# XMC4500.net
KiCad netlist of a schematic drawn in Altium Designer
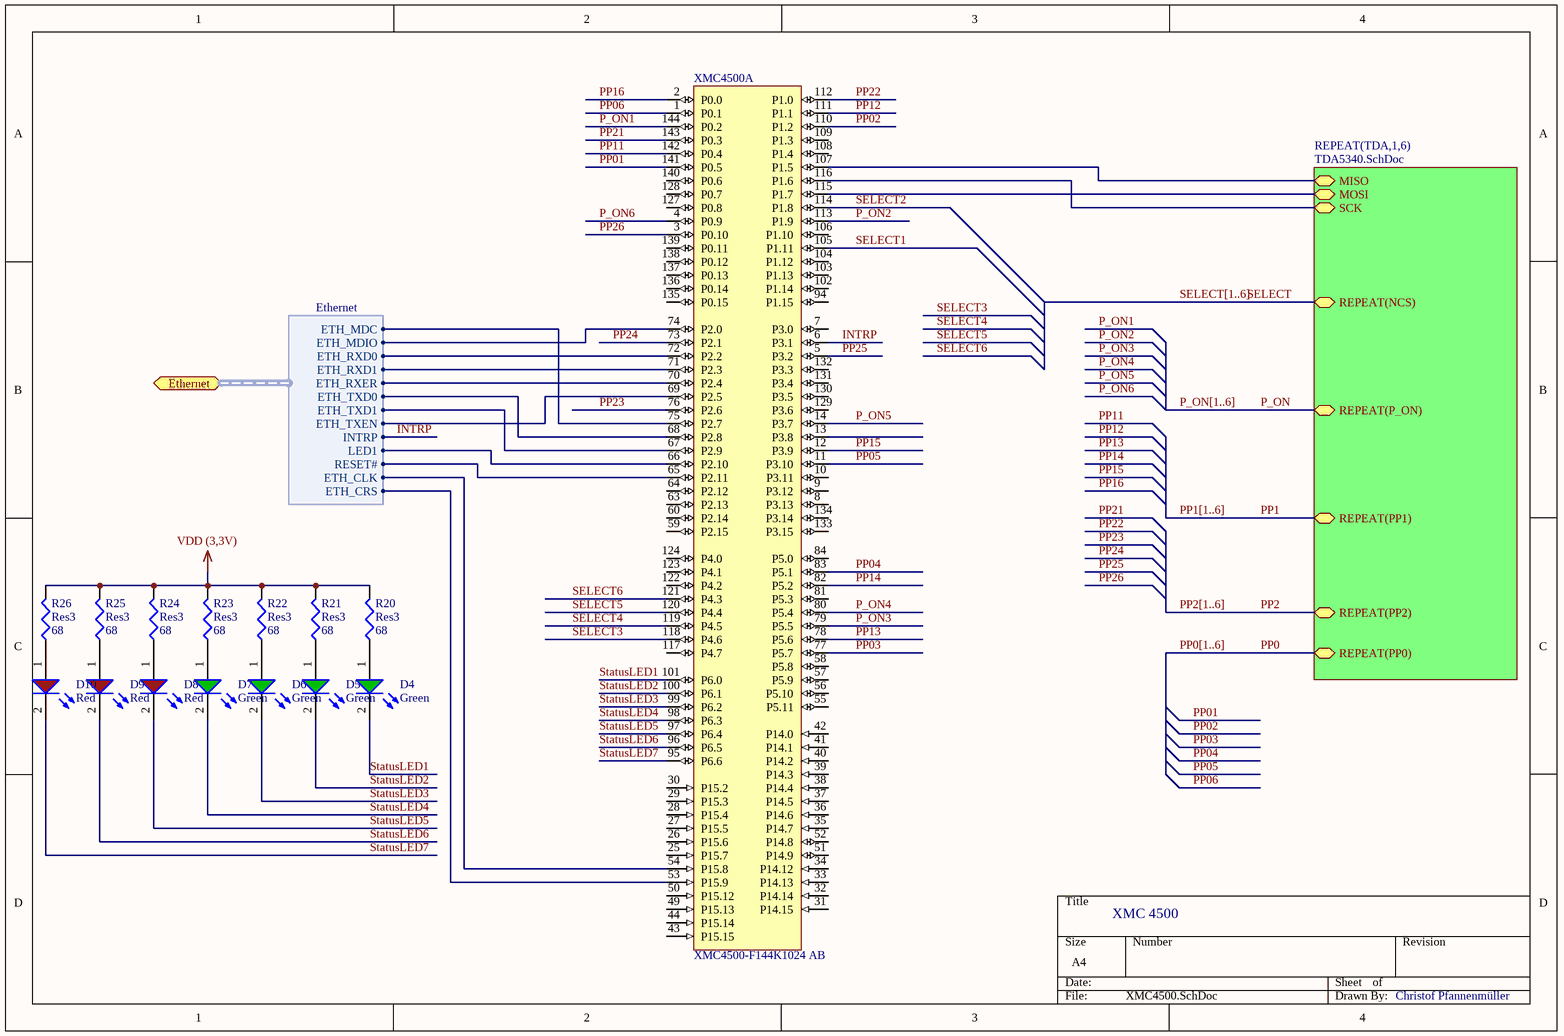
[diagram p0: XMC4500.SchDoc]

(export (version "E")
  (design (tool "Eeschema 10.0.6"))
  (components
    (comp (ref "D4")
      (value "Green")
      (footprint "LED_0805_Green")
      (description "SMD mono-color Chip LED, WL-SMCW, Green")
      (fields
        (field (name "PARTNO") "150080GS75000")
        (field (name "MANUFACTURER") "W黵th Elektronik eiSos GmbH")
        (field (name "CREATED BY") "Christin Otto")
      )
      (libsource (lib "WL-SMCW_rev15b") (part "WL-SMCW 0805  150080GS75000"))
    )
    (comp (ref "D5")
      (value "Green")
      (footprint "LED_0805_Green")
      (description "SMD mono-color Chip LED, WL-SMCW, Green")
      (fields
        (field (name "PARTNO") "150080GS75000")
        (field (name "MANUFACTURER") "W黵th Elektronik eiSos GmbH")
        (field (name "CREATED BY") "Christin Otto")
      )
      (libsource (lib "WL-SMCW_rev15b") (part "WL-SMCW 0805  150080GS75000"))
    )
    (comp (ref "D6")
      (value "Green")
      (footprint "LED_0805_Green")
      (description "SMD mono-color Chip LED, WL-SMCW, Green")
      (fields
        (field (name "PARTNO") "150080GS75000")
        (field (name "MANUFACTURER") "W黵th Elektronik eiSos GmbH")
        (field (name "CREATED BY") "Christin Otto")
      )
      (libsource (lib "WL-SMCW_rev15b") (part "WL-SMCW 0805  150080GS75000"))
    )
    (comp (ref "D7")
      (value "Green")
      (footprint "LED_0805_Green")
      (description "SMD mono-color Chip LED, WL-SMCW, Green")
      (fields
        (field (name "PARTNO") "150080GS75000")
        (field (name "MANUFACTURER") "W黵th Elektronik eiSos GmbH")
        (field (name "CREATED BY") "Christin Otto")
      )
      (libsource (lib "WL-SMCW_rev15b") (part "WL-SMCW 0805  150080GS75000"))
    )
    (comp (ref "D8")
      (value "Red")
      (footprint "LED_0805_Red")
      (description "SMD mono-color Chip LED, WL-SMCW, Red")
      (fields
        (field (name "PARTNO") "150080RS75000")
        (field (name "MANUFACTURER") "W黵th Elektronik eiSos GmbH")
        (field (name "CREATED BY") "Christin Otto")
      )
      (libsource (lib "WL-SMCW_rev15b") (part "WL-SMCW 0805  150080RS75000"))
    )
    (comp (ref "D9")
      (value "Red")
      (footprint "LED_0805_Red")
      (description "SMD mono-color Chip LED, WL-SMCW, Red")
      (fields
        (field (name "PARTNO") "150080RS75000")
        (field (name "MANUFACTURER") "W黵th Elektronik eiSos GmbH")
        (field (name "CREATED BY") "Christin Otto")
      )
      (libsource (lib "WL-SMCW_rev15b") (part "WL-SMCW 0805  150080RS75000"))
    )
    (comp (ref "D10")
      (value "Red")
      (footprint "LED_0805_Red")
      (description "SMD mono-color Chip LED, WL-SMCW, Red")
      (fields
        (field (name "PARTNO") "150080RS75000")
        (field (name "MANUFACTURER") "W黵th Elektronik eiSos GmbH")
        (field (name "CREATED BY") "Christin Otto")
      )
      (libsource (lib "WL-SMCW_rev15b") (part "WL-SMCW 0805  150080RS75000"))
    )
    (comp (ref "R20")
      (value "Res3")
      (footprint "J1-0603")
      (description "Resistor")
      (fields (field (name "ALTIUM_VALUE") "68") (field (name "PUBLISHER") "Altium Limited"))
      (libsource (lib "Miscellaneous Devices") (part "Res3"))
    )
    (comp (ref "R21")
      (value "Res3")
      (footprint "J1-0603")
      (description "Resistor")
      (fields (field (name "ALTIUM_VALUE") "68") (field (name "PUBLISHER") "Altium Limited"))
      (libsource (lib "Miscellaneous Devices") (part "Res3"))
    )
    (comp (ref "R22")
      (value "Res3")
      (footprint "J1-0603")
      (description "Resistor")
      (fields (field (name "ALTIUM_VALUE") "68") (field (name "PUBLISHER") "Altium Limited"))
      (libsource (lib "Miscellaneous Devices") (part "Res3"))
    )
    (comp (ref "R23")
      (value "Res3")
      (footprint "J1-0603")
      (description "Resistor")
      (fields (field (name "ALTIUM_VALUE") "68") (field (name "PUBLISHER") "Altium Limited"))
      (libsource (lib "Miscellaneous Devices") (part "Res3"))
    )
    (comp (ref "R24")
      (value "Res3")
      (footprint "J1-0603")
      (description "Resistor")
      (fields (field (name "ALTIUM_VALUE") "68") (field (name "PUBLISHER") "Altium Limited"))
      (libsource (lib "Miscellaneous Devices") (part "Res3"))
    )
    (comp (ref "R25")
      (value "Res3")
      (footprint "J1-0603")
      (description "Resistor")
      (fields (field (name "ALTIUM_VALUE") "68") (field (name "PUBLISHER") "Altium Limited"))
      (libsource (lib "Miscellaneous Devices") (part "Res3"))
    )
    (comp (ref "R26")
      (value "Res3")
      (footprint "J1-0603")
      (description "Resistor")
      (fields (field (name "ALTIUM_VALUE") "68") (field (name "PUBLISHER") "Altium Limited"))
      (libsource (lib "Miscellaneous Devices") (part "Res3"))
    )
    (comp (ref "XMC4500")
      (value "XMC4500-F144K1024 AB")
      (footprint "INF-PG-LQFP-144-18-6500X6500TP_N")
      (fields (field (name "MANUFACTURER") "Infineon"))
      (libsource (lib "Infineon XMC4000") (part "XMC4500-F144K1024 AB"))
    )
  )
  (nets
    (net (code "2") (name "/ETH_CLK") (class "Default")
      (node (ref "XMC4500") (pin "54") (pinfunction "P15.8_54") (pintype "input"))
    )
    (net (code "3") (name "/ETH_CRS") (class "Default")
      (node (ref "XMC4500") (pin "53") (pinfunction "P15.9_53") (pintype "input"))
    )
    (net (code "4") (name "/ETH_MDC") (class "Default")
      (node (ref "XMC4500") (pin "75") (pinfunction "P2.7_75") (pintype "bidirectional"))
    )
    (net (code "5") (name "/ETH_MDIO") (class "Default")
      (node (ref "XMC4500") (pin "74") (pinfunction "P2.0_74") (pintype "bidirectional"))
    )
    (net (code "6") (name "/ETH_RXD0") (class "Default")
      (node (ref "XMC4500") (pin "72") (pinfunction "P2.2_72") (pintype "bidirectional"))
    )
    (net (code "7") (name "/ETH_RXD1") (class "Default")
      (node (ref "XMC4500") (pin "71") (pinfunction "P2.3_71") (pintype "bidirectional"))
    )
    (net (code "8") (name "/ETH_RXER") (class "Default")
      (node (ref "XMC4500") (pin "70") (pinfunction "P2.4_70") (pintype "bidirectional"))
    )
    (net (code "9") (name "/ETH_TXD0") (class "Default")
      (node (ref "XMC4500") (pin "68") (pinfunction "P2.8_68") (pintype "bidirectional"))
    )
    (net (code "10") (name "/ETH_TXD1") (class "Default")
      (node (ref "XMC4500") (pin "67") (pinfunction "P2.9_67") (pintype "bidirectional"))
    )
    (net (code "11") (name "/ETH_TXEN") (class "Default")
      (node (ref "XMC4500") (pin "69") (pinfunction "P2.5_69") (pintype "bidirectional"))
    )
    (net (code "12") (name "/INTRP") (class "Default")
      (node (ref "XMC4500") (pin "6") (pinfunction "P3.1_6") (pintype "bidirectional"))
    )
    (net (code "13") (name "/LED1") (class "Default")
      (node (ref "XMC4500") (pin "66") (pinfunction "P2.10_66") (pintype "bidirectional"))
    )
    (net (code "14") (name "/MISO") (class "Default")
      (node (ref "XMC4500") (pin "107") (pinfunction "P1.5_107") (pintype "bidirectional"))
    )
    (net (code "15") (name "/MOSI") (class "Default")
      (node (ref "XMC4500") (pin "115") (pinfunction "P1.7_115") (pintype "bidirectional"))
    )
    (net (code "18") (name "/PP01") (class "Default")
      (node (ref "XMC4500") (pin "141") (pinfunction "P0.5_141") (pintype "bidirectional"))
    )
    (net (code "22") (name "/PP02") (class "Default")
      (node (ref "XMC4500") (pin "110") (pinfunction "P1.2_110") (pintype "bidirectional"))
    )
    (net (code "24") (name "/PP03") (class "Default")
      (node (ref "XMC4500") (pin "77") (pinfunction "P5.7_77") (pintype "bidirectional"))
    )
    (net (code "25") (name "/PP04") (class "Default")
      (node (ref "XMC4500") (pin "83") (pinfunction "P5.1_83") (pintype "bidirectional"))
    )
    (net (code "26") (name "/PP05") (class "Default")
      (node (ref "XMC4500") (pin "11") (pinfunction "P3.10_11") (pintype "bidirectional"))
    )
    (net (code "27") (name "/PP06") (class "Default")
      (node (ref "XMC4500") (pin "1") (pinfunction "P0.1_1") (pintype "bidirectional"))
    )
    (net (code "28") (name "/PP11") (class "Default")
      (node (ref "XMC4500") (pin "142") (pinfunction "P0.4_142") (pintype "bidirectional"))
    )
    (net (code "29") (name "/PP12") (class "Default")
      (node (ref "XMC4500") (pin "111") (pinfunction "P1.1_111") (pintype "bidirectional"))
    )
    (net (code "30") (name "/PP13") (class "Default")
      (node (ref "XMC4500") (pin "78") (pinfunction "P5.6_78") (pintype "bidirectional"))
    )
    (net (code "31") (name "/PP14") (class "Default")
      (node (ref "XMC4500") (pin "82") (pinfunction "P5.2_82") (pintype "bidirectional"))
    )
    (net (code "32") (name "/PP15") (class "Default")
      (node (ref "XMC4500") (pin "12") (pinfunction "P3.9_12") (pintype "bidirectional"))
    )
    (net (code "33") (name "/PP16") (class "Default")
      (node (ref "XMC4500") (pin "2") (pinfunction "P0.0_2") (pintype "bidirectional"))
    )
    (net (code "34") (name "/PP21") (class "Default")
      (node (ref "XMC4500") (pin "143") (pinfunction "P0.3_143") (pintype "bidirectional"))
    )
    (net (code "35") (name "/PP22") (class "Default")
      (node (ref "XMC4500") (pin "112") (pinfunction "P1.0_112") (pintype "bidirectional"))
    )
    (net (code "36") (name "/PP23") (class "Default")
      (node (ref "XMC4500") (pin "76") (pinfunction "P2.6_76") (pintype "bidirectional"))
    )
    (net (code "37") (name "/PP24") (class "Default")
      (node (ref "XMC4500") (pin "73") (pinfunction "P2.1_73") (pintype "bidirectional"))
    )
    (net (code "38") (name "/PP25") (class "Default")
      (node (ref "XMC4500") (pin "5") (pinfunction "P3.2_5") (pintype "bidirectional"))
    )
    (net (code "39") (name "/PP26") (class "Default")
      (node (ref "XMC4500") (pin "3") (pinfunction "P0.10_3") (pintype "bidirectional"))
    )
    (net (code "41") (name "/P_ON1") (class "Default")
      (node (ref "XMC4500") (pin "144") (pinfunction "P0.2_144") (pintype "bidirectional"))
    )
    (net (code "42") (name "/P_ON2") (class "Default")
      (node (ref "XMC4500") (pin "113") (pinfunction "P1.9_113") (pintype "bidirectional"))
    )
    (net (code "43") (name "/P_ON3") (class "Default")
      (node (ref "XMC4500") (pin "79") (pinfunction "P5.5_79") (pintype "bidirectional"))
    )
    (net (code "44") (name "/P_ON4") (class "Default")
      (node (ref "XMC4500") (pin "80") (pinfunction "P5.4_80") (pintype "bidirectional"))
    )
    (net (code "45") (name "/P_ON5") (class "Default")
      (node (ref "XMC4500") (pin "14") (pinfunction "P3.7_14") (pintype "bidirectional"))
    )
    (net (code "46") (name "/P_ON6") (class "Default")
      (node (ref "XMC4500") (pin "4") (pinfunction "P0.9_4") (pintype "bidirectional"))
    )
    (net (code "48") (name "/RESET#") (class "Default")
      (node (ref "XMC4500") (pin "65") (pinfunction "P2.11_65") (pintype "bidirectional"))
    )
    (net (code "49") (name "/SCK") (class "Default")
      (node (ref "XMC4500") (pin "116") (pinfunction "P1.6_116") (pintype "bidirectional"))
    )
    (net (code "51") (name "/SELECT1") (class "Default")
      (node (ref "XMC4500") (pin "105") (pinfunction "P1.11_105") (pintype "bidirectional"))
    )
    (net (code "52") (name "/SELECT2") (class "Default")
      (node (ref "XMC4500") (pin "114") (pinfunction "P1.8_114") (pintype "bidirectional"))
    )
    (net (code "53") (name "/SELECT3") (class "Default")
      (node (ref "XMC4500") (pin "118") (pinfunction "P4.6_118") (pintype "bidirectional"))
    )
    (net (code "54") (name "/SELECT4") (class "Default")
      (node (ref "XMC4500") (pin "119") (pinfunction "P4.5_119") (pintype "bidirectional"))
    )
    (net (code "55") (name "/SELECT5") (class "Default")
      (node (ref "XMC4500") (pin "120") (pinfunction "P4.4_120") (pintype "bidirectional"))
    )
    (net (code "56") (name "/SELECT6") (class "Default")
      (node (ref "XMC4500") (pin "121") (pinfunction "P4.3_121") (pintype "bidirectional"))
    )
    (net (code "58") (name "/StatusLED1") (class "Default")
      (node (ref "D4") (pin "2") (pinfunction "C_2") (pintype "passive"))
      (node (ref "XMC4500") (pin "101") (pinfunction "P6.0_101") (pintype "bidirectional"))
    )
    (net (code "59") (name "/StatusLED2") (class "Default")
      (node (ref "D5") (pin "2") (pinfunction "C_2") (pintype "passive"))
      (node (ref "XMC4500") (pin "100") (pinfunction "P6.1_100") (pintype "bidirectional"))
    )
    (net (code "60") (name "/StatusLED3") (class "Default")
      (node (ref "D6") (pin "2") (pinfunction "C_2") (pintype "passive"))
      (node (ref "XMC4500") (pin "99") (pinfunction "P6.2_99") (pintype "bidirectional"))
    )
    (net (code "61") (name "/StatusLED4") (class "Default")
      (node (ref "D7") (pin "2") (pinfunction "C_2") (pintype "passive"))
      (node (ref "XMC4500") (pin "98") (pinfunction "P6.3_98") (pintype "bidirectional"))
    )
    (net (code "62") (name "/StatusLED5") (class "Default")
      (node (ref "D8") (pin "2") (pinfunction "C_2") (pintype "passive"))
      (node (ref "XMC4500") (pin "97") (pinfunction "P6.4_97") (pintype "bidirectional"))
    )
    (net (code "63") (name "/StatusLED6") (class "Default")
      (node (ref "D9") (pin "2") (pinfunction "C_2") (pintype "passive"))
      (node (ref "XMC4500") (pin "96") (pinfunction "P6.5_96") (pintype "bidirectional"))
    )
    (net (code "64") (name "/StatusLED7") (class "Default")
      (node (ref "D10") (pin "2") (pinfunction "C_2") (pintype "passive"))
      (node (ref "XMC4500") (pin "95") (pinfunction "P6.6_95") (pintype "bidirectional"))
    )
    (net (code "66") (name "Net-(D4-A)") (class "Default")
      (node (ref "D4") (pin "1") (pinfunction "A_1") (pintype "passive"))
      (node (ref "R20") (pin "1") (pinfunction "1_1") (pintype "passive"))
    )
    (net (code "67") (name "Net-(D5-A)") (class "Default")
      (node (ref "D5") (pin "1") (pinfunction "A_1") (pintype "passive"))
      (node (ref "R21") (pin "1") (pinfunction "1_1") (pintype "passive"))
    )
    (net (code "68") (name "Net-(D6-A)") (class "Default")
      (node (ref "D6") (pin "1") (pinfunction "A_1") (pintype "passive"))
      (node (ref "R22") (pin "1") (pinfunction "1_1") (pintype "passive"))
    )
    (net (code "69") (name "Net-(D7-A)") (class "Default")
      (node (ref "D7") (pin "1") (pinfunction "A_1") (pintype "passive"))
      (node (ref "R23") (pin "1") (pinfunction "1_1") (pintype "passive"))
    )
    (net (code "70") (name "Net-(D8-A)") (class "Default")
      (node (ref "D8") (pin "1") (pinfunction "A_1") (pintype "passive"))
      (node (ref "R24") (pin "1") (pinfunction "1_1") (pintype "passive"))
    )
    (net (code "71") (name "Net-(D9-A)") (class "Default")
      (node (ref "D9") (pin "1") (pinfunction "A_1") (pintype "passive"))
      (node (ref "R25") (pin "1") (pinfunction "1_1") (pintype "passive"))
    )
    (net (code "72") (name "Net-(D10-A)") (class "Default")
      (node (ref "D10") (pin "1") (pinfunction "A_1") (pintype "passive"))
      (node (ref "R26") (pin "1") (pinfunction "1_1") (pintype "passive"))
    )
    (net (code "73") (name "VDD (3,3V)") (class "Default")
      (node (ref "R20") (pin "2") (pinfunction "2_2") (pintype "passive"))
      (node (ref "R21") (pin "2") (pinfunction "2_2") (pintype "passive"))
      (node (ref "R22") (pin "2") (pinfunction "2_2") (pintype "passive"))
      (node (ref "R23") (pin "2") (pinfunction "2_2") (pintype "passive"))
      (node (ref "R24") (pin "2") (pinfunction "2_2") (pintype "passive"))
      (node (ref "R25") (pin "2") (pinfunction "2_2") (pintype "passive"))
      (node (ref "R26") (pin "2") (pinfunction "2_2") (pintype "passive"))
    )
    (net (code "74") (name "unconnected-(XMC4500A-P0.6-Pad140)") (class "Default")
      (node (ref "XMC4500") (pin "140") (pinfunction "P0.6_140") (pintype "bidirectional"))
    )
    (net (code "75") (name "unconnected-(XMC4500A-P0.7-Pad128)") (class "Default")
      (node (ref "XMC4500") (pin "128") (pinfunction "P0.7_128") (pintype "bidirectional"))
    )
    (net (code "76") (name "unconnected-(XMC4500A-P0.8-Pad127)") (class "Default")
      (node (ref "XMC4500") (pin "127") (pinfunction "P0.8_127") (pintype "bidirectional"))
    )
    (net (code "77") (name "unconnected-(XMC4500A-P0.11-Pad139)") (class "Default")
      (node (ref "XMC4500") (pin "139") (pinfunction "P0.11_139") (pintype "bidirectional"))
    )
    (net (code "78") (name "unconnected-(XMC4500A-P0.12-Pad138)") (class "Default")
      (node (ref "XMC4500") (pin "138") (pinfunction "P0.12_138") (pintype "bidirectional"))
    )
    (net (code "79") (name "unconnected-(XMC4500A-P0.13-Pad137)") (class "Default")
      (node (ref "XMC4500") (pin "137") (pinfunction "P0.13_137") (pintype "bidirectional"))
    )
    (net (code "80") (name "unconnected-(XMC4500A-P0.14-Pad136)") (class "Default")
      (node (ref "XMC4500") (pin "136") (pinfunction "P0.14_136") (pintype "bidirectional"))
    )
    (net (code "81") (name "unconnected-(XMC4500A-P0.15-Pad135)") (class "Default")
      (node (ref "XMC4500") (pin "135") (pinfunction "P0.15_135") (pintype "bidirectional"))
    )
    (net (code "82") (name "unconnected-(XMC4500A-P1.3-Pad109)") (class "Default")
      (node (ref "XMC4500") (pin "109") (pinfunction "P1.3_109") (pintype "bidirectional"))
    )
    (net (code "83") (name "unconnected-(XMC4500A-P1.4-Pad108)") (class "Default")
      (node (ref "XMC4500") (pin "108") (pinfunction "P1.4_108") (pintype "bidirectional"))
    )
    (net (code "84") (name "unconnected-(XMC4500A-P1.10-Pad106)") (class "Default")
      (node (ref "XMC4500") (pin "106") (pinfunction "P1.10_106") (pintype "bidirectional"))
    )
    (net (code "85") (name "unconnected-(XMC4500A-P1.12-Pad104)") (class "Default")
      (node (ref "XMC4500") (pin "104") (pinfunction "P1.12_104") (pintype "bidirectional"))
    )
    (net (code "86") (name "unconnected-(XMC4500A-P1.13-Pad103)") (class "Default")
      (node (ref "XMC4500") (pin "103") (pinfunction "P1.13_103") (pintype "bidirectional"))
    )
    (net (code "87") (name "unconnected-(XMC4500A-P1.14-Pad102)") (class "Default")
      (node (ref "XMC4500") (pin "102") (pinfunction "P1.14_102") (pintype "bidirectional"))
    )
    (net (code "88") (name "unconnected-(XMC4500A-P1.15-Pad94)") (class "Default")
      (node (ref "XMC4500") (pin "94") (pinfunction "P1.15_94") (pintype "bidirectional"))
    )
    (net (code "89") (name "unconnected-(XMC4500A-P2.12-Pad64)") (class "Default")
      (node (ref "XMC4500") (pin "64") (pinfunction "P2.12_64") (pintype "bidirectional"))
    )
    (net (code "90") (name "unconnected-(XMC4500A-P2.13-Pad63)") (class "Default")
      (node (ref "XMC4500") (pin "63") (pinfunction "P2.13_63") (pintype "bidirectional"))
    )
    (net (code "91") (name "unconnected-(XMC4500A-P2.14-Pad60)") (class "Default")
      (node (ref "XMC4500") (pin "60") (pinfunction "P2.14_60") (pintype "bidirectional"))
    )
    (net (code "92") (name "unconnected-(XMC4500A-P2.15-Pad59)") (class "Default")
      (node (ref "XMC4500") (pin "59") (pinfunction "P2.15_59") (pintype "bidirectional"))
    )
    (net (code "93") (name "unconnected-(XMC4500A-P3.0-Pad7)") (class "Default")
      (node (ref "XMC4500") (pin "7") (pinfunction "P3.0_7") (pintype "bidirectional"))
    )
    (net (code "94") (name "unconnected-(XMC4500A-P3.3-Pad132)") (class "Default")
      (node (ref "XMC4500") (pin "132") (pinfunction "P3.3_132") (pintype "bidirectional"))
    )
    (net (code "95") (name "unconnected-(XMC4500A-P3.4-Pad131)") (class "Default")
      (node (ref "XMC4500") (pin "131") (pinfunction "P3.4_131") (pintype "bidirectional"))
    )
    (net (code "96") (name "unconnected-(XMC4500A-P3.5-Pad130)") (class "Default")
      (node (ref "XMC4500") (pin "130") (pinfunction "P3.5_130") (pintype "bidirectional"))
    )
    (net (code "97") (name "unconnected-(XMC4500A-P3.6-Pad129)") (class "Default")
      (node (ref "XMC4500") (pin "129") (pinfunction "P3.6_129") (pintype "bidirectional"))
    )
    (net (code "98") (name "unconnected-(XMC4500A-P3.8-Pad13)") (class "Default")
      (node (ref "XMC4500") (pin "13") (pinfunction "P3.8_13") (pintype "bidirectional"))
    )
    (net (code "99") (name "unconnected-(XMC4500A-P3.11-Pad10)") (class "Default")
      (node (ref "XMC4500") (pin "10") (pinfunction "P3.11_10") (pintype "bidirectional"))
    )
    (net (code "100") (name "unconnected-(XMC4500A-P3.12-Pad9)") (class "Default")
      (node (ref "XMC4500") (pin "9") (pinfunction "P3.12_9") (pintype "bidirectional"))
    )
    (net (code "101") (name "unconnected-(XMC4500A-P3.13-Pad8)") (class "Default")
      (node (ref "XMC4500") (pin "8") (pinfunction "P3.13_8") (pintype "bidirectional"))
    )
    (net (code "102") (name "unconnected-(XMC4500A-P3.14-Pad134)") (class "Default")
      (node (ref "XMC4500") (pin "134") (pinfunction "P3.14_134") (pintype "bidirectional"))
    )
    (net (code "103") (name "unconnected-(XMC4500A-P3.15-Pad133)") (class "Default")
      (node (ref "XMC4500") (pin "133") (pinfunction "P3.15_133") (pintype "bidirectional"))
    )
    (net (code "104") (name "unconnected-(XMC4500A-P4.0-Pad124)") (class "Default")
      (node (ref "XMC4500") (pin "124") (pinfunction "P4.0_124") (pintype "bidirectional"))
    )
    (net (code "105") (name "unconnected-(XMC4500A-P4.1-Pad123)") (class "Default")
      (node (ref "XMC4500") (pin "123") (pinfunction "P4.1_123") (pintype "bidirectional"))
    )
    (net (code "106") (name "unconnected-(XMC4500A-P4.2-Pad122)") (class "Default")
      (node (ref "XMC4500") (pin "122") (pinfunction "P4.2_122") (pintype "bidirectional"))
    )
    (net (code "107") (name "unconnected-(XMC4500A-P4.7-Pad117)") (class "Default")
      (node (ref "XMC4500") (pin "117") (pinfunction "P4.7_117") (pintype "bidirectional"))
    )
    (net (code "108") (name "unconnected-(XMC4500A-P5.0-Pad84)") (class "Default")
      (node (ref "XMC4500") (pin "84") (pinfunction "P5.0_84") (pintype "bidirectional"))
    )
    (net (code "109") (name "unconnected-(XMC4500A-P5.3-Pad81)") (class "Default")
      (node (ref "XMC4500") (pin "81") (pinfunction "P5.3_81") (pintype "bidirectional"))
    )
    (net (code "110") (name "unconnected-(XMC4500A-P5.8-Pad58)") (class "Default")
      (node (ref "XMC4500") (pin "58") (pinfunction "P5.8_58") (pintype "bidirectional"))
    )
    (net (code "111") (name "unconnected-(XMC4500A-P5.9-Pad57)") (class "Default")
      (node (ref "XMC4500") (pin "57") (pinfunction "P5.9_57") (pintype "bidirectional"))
    )
    (net (code "112") (name "unconnected-(XMC4500A-P5.10-Pad56)") (class "Default")
      (node (ref "XMC4500") (pin "56") (pinfunction "P5.10_56") (pintype "bidirectional"))
    )
    (net (code "113") (name "unconnected-(XMC4500A-P5.11-Pad55)") (class "Default")
      (node (ref "XMC4500") (pin "55") (pinfunction "P5.11_55") (pintype "bidirectional"))
    )
    (net (code "114") (name "unconnected-(XMC4500A-P14.0-Pad42)") (class "Default")
      (node (ref "XMC4500") (pin "42") (pinfunction "P14.0_42") (pintype "input"))
    )
    (net (code "115") (name "unconnected-(XMC4500A-P14.1-Pad41)") (class "Default")
      (node (ref "XMC4500") (pin "41") (pinfunction "P14.1_41") (pintype "input"))
    )
    (net (code "116") (name "unconnected-(XMC4500A-P14.2-Pad40)") (class "Default")
      (node (ref "XMC4500") (pin "40") (pinfunction "P14.2_40") (pintype "input"))
    )
    (net (code "117") (name "unconnected-(XMC4500A-P14.3-Pad39)") (class "Default")
      (node (ref "XMC4500") (pin "39") (pinfunction "P14.3_39") (pintype "input"))
    )
    (net (code "118") (name "unconnected-(XMC4500A-P14.4-Pad38)") (class "Default")
      (node (ref "XMC4500") (pin "38") (pinfunction "P14.4_38") (pintype "input"))
    )
    (net (code "119") (name "unconnected-(XMC4500A-P14.5-Pad37)") (class "Default")
      (node (ref "XMC4500") (pin "37") (pinfunction "P14.5_37") (pintype "input"))
    )
    (net (code "120") (name "unconnected-(XMC4500A-P14.6-Pad36)") (class "Default")
      (node (ref "XMC4500") (pin "36") (pinfunction "P14.6_36") (pintype "input"))
    )
    (net (code "121") (name "unconnected-(XMC4500A-P14.7-Pad35)") (class "Default")
      (node (ref "XMC4500") (pin "35") (pinfunction "P14.7_35") (pintype "input"))
    )
    (net (code "122") (name "unconnected-(XMC4500A-P14.8-Pad52)") (class "Default")
      (node (ref "XMC4500") (pin "52") (pinfunction "P14.8_52") (pintype "bidirectional"))
    )
    (net (code "123") (name "unconnected-(XMC4500A-P14.9-Pad51)") (class "Default")
      (node (ref "XMC4500") (pin "51") (pinfunction "P14.9_51") (pintype "bidirectional"))
    )
    (net (code "124") (name "unconnected-(XMC4500A-P14.12-Pad34)") (class "Default")
      (node (ref "XMC4500") (pin "34") (pinfunction "P14.12_34") (pintype "input"))
    )
    (net (code "125") (name "unconnected-(XMC4500A-P14.13-Pad33)") (class "Default")
      (node (ref "XMC4500") (pin "33") (pinfunction "P14.13_33") (pintype "input"))
    )
    (net (code "126") (name "unconnected-(XMC4500A-P14.14-Pad32)") (class "Default")
      (node (ref "XMC4500") (pin "32") (pinfunction "P14.14_32") (pintype "input"))
    )
    (net (code "127") (name "unconnected-(XMC4500A-P14.15-Pad31)") (class "Default")
      (node (ref "XMC4500") (pin "31") (pinfunction "P14.15_31") (pintype "input"))
    )
    (net (code "128") (name "unconnected-(XMC4500A-P15.2-Pad30)") (class "Default")
      (node (ref "XMC4500") (pin "30") (pinfunction "P15.2_30") (pintype "input"))
    )
    (net (code "129") (name "unconnected-(XMC4500A-P15.3-Pad29)") (class "Default")
      (node (ref "XMC4500") (pin "29") (pinfunction "P15.3_29") (pintype "input"))
    )
    (net (code "130") (name "unconnected-(XMC4500A-P15.4-Pad28)") (class "Default")
      (node (ref "XMC4500") (pin "28") (pinfunction "P15.4_28") (pintype "input"))
    )
    (net (code "131") (name "unconnected-(XMC4500A-P15.5-Pad27)") (class "Default")
      (node (ref "XMC4500") (pin "27") (pinfunction "P15.5_27") (pintype "input"))
    )
    (net (code "132") (name "unconnected-(XMC4500A-P15.6-Pad26)") (class "Default")
      (node (ref "XMC4500") (pin "26") (pinfunction "P15.6_26") (pintype "input"))
    )
    (net (code "133") (name "unconnected-(XMC4500A-P15.7-Pad25)") (class "Default")
      (node (ref "XMC4500") (pin "25") (pinfunction "P15.7_25") (pintype "input"))
    )
    (net (code "134") (name "unconnected-(XMC4500A-P15.12-Pad50)") (class "Default")
      (node (ref "XMC4500") (pin "50") (pinfunction "P15.12_50") (pintype "input"))
    )
    (net (code "135") (name "unconnected-(XMC4500A-P15.13-Pad49)") (class "Default")
      (node (ref "XMC4500") (pin "49") (pinfunction "P15.13_49") (pintype "input"))
    )
    (net (code "136") (name "unconnected-(XMC4500A-P15.14-Pad44)") (class "Default")
      (node (ref "XMC4500") (pin "44") (pinfunction "P15.14_44") (pintype "input"))
    )
    (net (code "137") (name "unconnected-(XMC4500A-P15.15-Pad43)") (class "Default")
      (node (ref "XMC4500") (pin "43") (pinfunction "P15.15_43") (pintype "input"))
    )
  )
)
